# P_loha_E.net
KiCad netlist of a schematic drawn in EasyEDA Pro
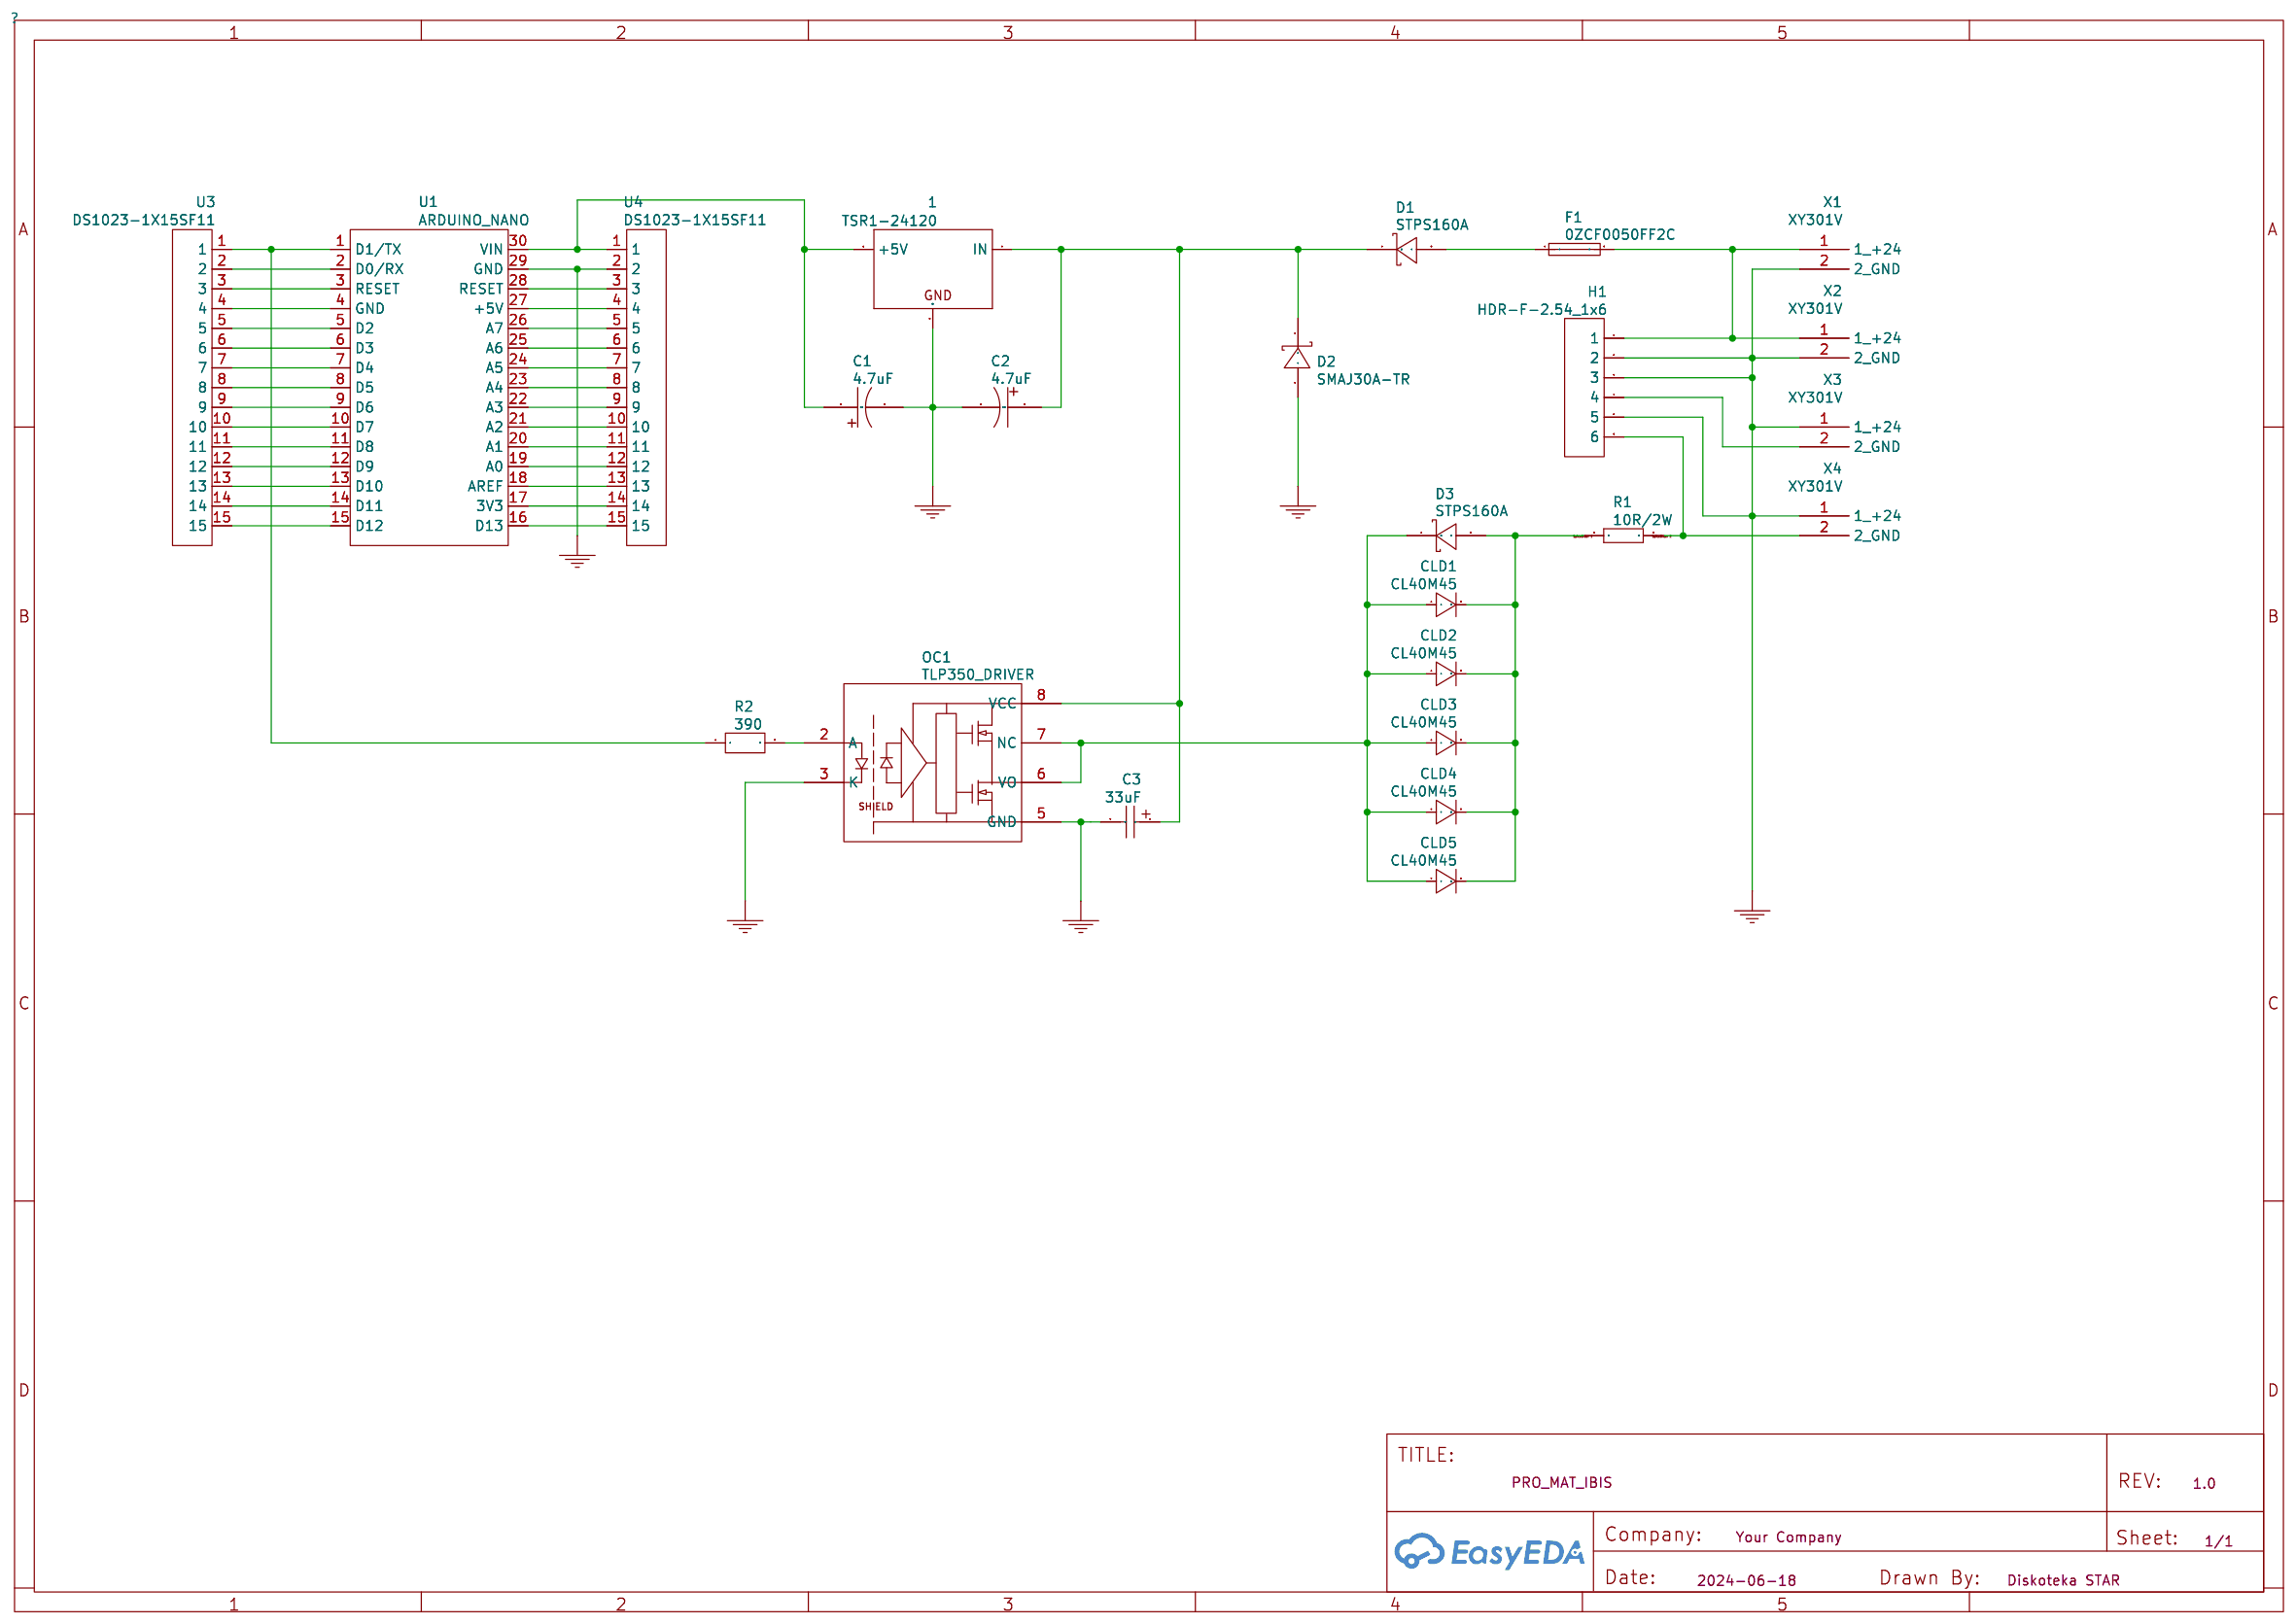
[diagram p0: schematic sheet]

(export (version "E")
  (design (tool "Eeschema 10.0.6"))
  (components
    (comp (ref "1") (value "TSR1-24120") (libsource (lib "easyedapro") (part "TSR1-24120")))
    (comp (ref "C1")
      (value "4.7uF")
      (fields
        (field (name "Manufacturer Part") "293D475X9035B2TE3")
        (field (name "Manufacturer") "VISHAY(威世)")
      )
      (libsource (lib "easyedapro") (part "4.7uF"))
    )
    (comp (ref "C2")
      (value "4.7uF")
      (fields
        (field (name "Manufacturer Part") "293D475X9035B2TE3")
        (field (name "Manufacturer") "VISHAY(威世)")
      )
      (libsource (lib "easyedapro") (part "4.7uF"))
    )
    (comp (ref "C3")
      (value "33uF")
      (fields
        (field (name "Manufacturer Part") "TPSD336K035R0300")
        (field (name "Manufacturer") "Kyocera AVX")
      )
      (libsource (lib "easyedapro") (part "33uF"))
    )
    (comp (ref "CLD1")
      (value "CL40M45")
      (fields (field (name "Manufacturer Part") "LL4148-GS08") (field (name "Manufacturer") "DIO"))
      (libsource (lib "easyedapro") (part "CL40M45"))
    )
    (comp (ref "CLD2")
      (value "CL40M45")
      (fields (field (name "Manufacturer Part") "LL4148-GS08") (field (name "Manufacturer") "DIO"))
      (libsource (lib "easyedapro") (part "CL40M45"))
    )
    (comp (ref "CLD3")
      (value "CL40M45")
      (fields (field (name "Manufacturer Part") "LL4148-GS08") (field (name "Manufacturer") "DIO"))
      (libsource (lib "easyedapro") (part "CL40M45"))
    )
    (comp (ref "CLD4")
      (value "CL40M45")
      (fields (field (name "Manufacturer Part") "LL4148-GS08") (field (name "Manufacturer") "DIO"))
      (libsource (lib "easyedapro") (part "CL40M45"))
    )
    (comp (ref "CLD5")
      (value "CL40M45")
      (fields (field (name "Manufacturer Part") "LL4148-GS08") (field (name "Manufacturer") "DIO"))
      (libsource (lib "easyedapro") (part "CL40M45"))
    )
    (comp (ref "D1")
      (value "STPS160A")
      (fields (field (name "Manufacturer") "ST(意法半导体)"))
      (libsource (lib "easyedapro") (part "STPS160A"))
    )
    (comp (ref "D2")
      (value "SMAJ30A-TR")
      (fields (field (name "Manufacturer") "ST(意法半导体)"))
      (libsource (lib "easyedapro") (part "SMAJ30A-TR"))
    )
    (comp (ref "D3")
      (value "STPS160A")
      (fields (field (name "Manufacturer") "ST(意法半导体)"))
      (libsource (lib "easyedapro") (part "STPS160A"))
    )
    (comp (ref "F1")
      (value "0ZCF0050FF2C")
      (fields (field (name "Manufacturer Part") "530-0ZCF0050FF2C") (field (name "Manufacturer") "Bel Fuse"))
      (libsource (lib "easyedapro") (part "0ZCF0050FF2C"))
    )
    (comp (ref "H1") (value "HDR-F-2.54_1x6") (libsource (lib "easyedapro") (part "HDR-F-2.54_1x6")))
    (comp (ref "OC1")
      (value "TLP350_DRIVER")
      (fields (field (name "Manufacturer Part") "TLP350(F)") (field (name "Manufacturer") "TOSHIBA(东芝)"))
      (libsource (lib "easyedapro") (part "TLP350_DRIVER"))
    )
    (comp (ref "R1") (value "10R/2W") (libsource (lib "easyedapro") (part "10R/2W")))
    (comp (ref "R2") (value "390") (libsource (lib "easyedapro") (part "390")))
    (comp (ref "U1") (value "ARDUINO_NANO") (libsource (lib "easyedapro") (part "ARDUINO_NANO")))
    (comp (ref "U3")
      (value "DS1023-1X15SF11")
      (fields (field (name "Manufacturer Part") "DS1023-1x15SF11") (field (name "Manufacturer") "CONNFLY"))
      (libsource (lib "easyedapro") (part "DS1023-1X15SF11"))
    )
    (comp (ref "U4")
      (value "DS1023-1X15SF11")
      (fields (field (name "Manufacturer Part") "DS1023-1x15SF11") (field (name "Manufacturer") "CONNFLY"))
      (libsource (lib "") (part "DS1023-1X15SF11_1"))
    )
    (comp (ref "X1")
      (value "XY301V")
      (fields
        (field (name "Manufacturer Part") "XY301V-A-5.0-2P")
        (field (name "Manufacturer") "XINLAIYA(新莱亚)")
      )
      (libsource (lib "easyedapro") (part "XY301V"))
    )
    (comp (ref "X2")
      (value "XY301V")
      (fields
        (field (name "Manufacturer Part") "XY301V-A-5.0-2P")
        (field (name "Manufacturer") "XINLAIYA(新莱亚)")
      )
      (libsource (lib "easyedapro") (part "XY301V"))
    )
    (comp (ref "X3")
      (value "XY301V")
      (fields
        (field (name "Manufacturer Part") "XY301V-A-5.0-2P")
        (field (name "Manufacturer") "XINLAIYA(新莱亚)")
      )
      (libsource (lib "easyedapro") (part "XY301V"))
    )
    (comp (ref "X4")
      (value "XY301V")
      (fields
        (field (name "Manufacturer Part") "XY301V-A-5.0-2P")
        (field (name "Manufacturer") "XINLAIYA(新莱亚)")
      )
      (libsource (lib "easyedapro") (part "XY301V"))
    )
  )
  (nets
    (net (code "1") (name "GND") (class "Default")
      (node (ref "1") (pin "2") (pinfunction "GND_2") (pintype "bidirectional"))
      (node (ref "C1") (pin "2") (pinfunction "2_2") (pintype "unspecified"))
      (node (ref "C2") (pin "2") (pinfunction "2_2") (pintype "unspecified"))
      (node (ref "C3") (pin "2") (pinfunction "2_2") (pintype "input"))
      (node (ref "D2") (pin "2") (pinfunction "A_2") (pintype "unspecified"))
      (node (ref "H1") (pin "2") (pinfunction "2_2") (pintype "input"))
      (node (ref "H1") (pin "3") (pinfunction "3_3") (pintype "input"))
      (node (ref "H1") (pin "5") (pinfunction "5_5") (pintype "input"))
      (node (ref "OC1") (pin "3") (pinfunction "K_3") (pintype "unspecified"))
      (node (ref "OC1") (pin "5") (pinfunction "GND_5") (pintype "unspecified"))
      (node (ref "U1") (pin "29") (pinfunction "GND_29") (pintype "unspecified"))
      (node (ref "U4") (pin "2") (pinfunction "2_2") (pintype "unspecified"))
      (node (ref "X1") (pin "2") (pinfunction "2_GND_2") (pintype "unspecified"))
      (node (ref "X2") (pin "2") (pinfunction "2_GND_2") (pintype "unspecified"))
      (node (ref "X3") (pin "1") (pinfunction "1_+24_1") (pintype "unspecified"))
      (node (ref "X4") (pin "1") (pinfunction "1_+24_1") (pintype "unspecified"))
    )
    (net (code "2") (name "Net-(1-+5V)") (class "Default")
      (node (ref "1") (pin "3") (pinfunction "+5V_3") (pintype "bidirectional"))
      (node (ref "C1") (pin "1") (pinfunction "1_1") (pintype "unspecified"))
      (node (ref "U1") (pin "30") (pinfunction "VIN_30") (pintype "unspecified"))
      (node (ref "U4") (pin "1") (pinfunction "1_1") (pintype "unspecified"))
    )
    (net (code "3") (name "Net-(1-IN)") (class "Default")
      (node (ref "1") (pin "1") (pinfunction "IN_1") (pintype "bidirectional"))
      (node (ref "C2") (pin "1") (pinfunction "1_1") (pintype "unspecified"))
      (node (ref "C3") (pin "1") (pinfunction "1_1") (pintype "input"))
      (node (ref "D1") (pin "1") (pinfunction "C_1") (pintype "unspecified"))
      (node (ref "D2") (pin "1") (pinfunction "K_1") (pintype "unspecified"))
      (node (ref "OC1") (pin "8") (pinfunction "VCC_8") (pintype "unspecified"))
    )
    (net (code "4") (name "Net-(CLD1-A)") (class "Default")
      (node (ref "CLD1") (pin "1") (pinfunction "A_1") (pintype "unspecified"))
      (node (ref "CLD2") (pin "1") (pinfunction "A_1") (pintype "unspecified"))
      (node (ref "CLD3") (pin "1") (pinfunction "A_1") (pintype "unspecified"))
      (node (ref "CLD4") (pin "1") (pinfunction "A_1") (pintype "unspecified"))
      (node (ref "CLD5") (pin "1") (pinfunction "A_1") (pintype "unspecified"))
      (node (ref "D3") (pin "1") (pinfunction "C_1") (pintype "unspecified"))
      (node (ref "OC1") (pin "6") (pinfunction "VO_6") (pintype "unspecified"))
      (node (ref "OC1") (pin "7") (pinfunction "NC_7") (pintype "unspecified"))
    )
    (net (code "5") (name "Net-(CLD1-C)") (class "Default")
      (node (ref "CLD1") (pin "2") (pinfunction "C_2") (pintype "unspecified"))
      (node (ref "CLD2") (pin "2") (pinfunction "C_2") (pintype "unspecified"))
      (node (ref "CLD3") (pin "2") (pinfunction "C_2") (pintype "unspecified"))
      (node (ref "CLD4") (pin "2") (pinfunction "C_2") (pintype "unspecified"))
      (node (ref "CLD5") (pin "2") (pinfunction "C_2") (pintype "unspecified"))
      (node (ref "D3") (pin "2") (pinfunction "A_2") (pintype "unspecified"))
      (node (ref "R1") (pin "1") (pinfunction "1_1") (pintype "bidirectional"))
    )
    (net (code "6") (name "Net-(D1-A)") (class "Default")
      (node (ref "D1") (pin "2") (pinfunction "A_2") (pintype "unspecified"))
      (node (ref "F1") (pin "1") (pinfunction "1_1") (pintype "unspecified"))
    )
    (net (code "7") (name "Net-(OC1-A)") (class "Default")
      (node (ref "OC1") (pin "2") (pinfunction "A_2") (pintype "unspecified"))
      (node (ref "R2") (pin "2") (pinfunction "2_2") (pintype "unspecified"))
    )
    (net (code "8") (name "Net-(U1-+5V)") (class "Default")
      (node (ref "U1") (pin "27") (pinfunction "+5V_27") (pintype "unspecified"))
      (node (ref "U4") (pin "4") (pinfunction "4_4") (pintype "unspecified"))
    )
    (net (code "9") (name "Net-(U1-3V3)") (class "Default")
      (node (ref "U1") (pin "17") (pinfunction "3V3_17") (pintype "unspecified"))
      (node (ref "U4") (pin "14") (pinfunction "14_14") (pintype "unspecified"))
    )
    (net (code "10") (name "Net-(U1-A0)") (class "Default")
      (node (ref "U1") (pin "19") (pinfunction "A0_19") (pintype "unspecified"))
      (node (ref "U4") (pin "12") (pinfunction "12_12") (pintype "unspecified"))
    )
    (net (code "11") (name "Net-(U1-A1)") (class "Default")
      (node (ref "U1") (pin "20") (pinfunction "A1_20") (pintype "unspecified"))
      (node (ref "U4") (pin "11") (pinfunction "11_11") (pintype "unspecified"))
    )
    (net (code "12") (name "Net-(U1-A2)") (class "Default")
      (node (ref "U1") (pin "21") (pinfunction "A2_21") (pintype "unspecified"))
      (node (ref "U4") (pin "10") (pinfunction "10_10") (pintype "unspecified"))
    )
    (net (code "13") (name "Net-(U1-A3)") (class "Default")
      (node (ref "U1") (pin "22") (pinfunction "A3_22") (pintype "unspecified"))
      (node (ref "U4") (pin "9") (pinfunction "9_9") (pintype "unspecified"))
    )
    (net (code "14") (name "Net-(U1-A4)") (class "Default")
      (node (ref "U1") (pin "23") (pinfunction "A4_23") (pintype "unspecified"))
      (node (ref "U4") (pin "8") (pinfunction "8_8") (pintype "unspecified"))
    )
    (net (code "15") (name "Net-(U1-A5)") (class "Default")
      (node (ref "U1") (pin "24") (pinfunction "A5_24") (pintype "unspecified"))
      (node (ref "U4") (pin "7") (pinfunction "7_7") (pintype "unspecified"))
    )
    (net (code "16") (name "Net-(U1-A6)") (class "Default")
      (node (ref "U1") (pin "25") (pinfunction "A6_25") (pintype "unspecified"))
      (node (ref "U4") (pin "6") (pinfunction "6_6") (pintype "unspecified"))
    )
    (net (code "17") (name "Net-(U1-A7)") (class "Default")
      (node (ref "U1") (pin "26") (pinfunction "A7_26") (pintype "unspecified"))
      (node (ref "U4") (pin "5") (pinfunction "5_5") (pintype "unspecified"))
    )
    (net (code "18") (name "Net-(U1-AREF)") (class "Default")
      (node (ref "U1") (pin "18") (pinfunction "AREF_18") (pintype "unspecified"))
      (node (ref "U4") (pin "13") (pinfunction "13_13") (pintype "unspecified"))
    )
    (net (code "19") (name "Net-(U1-D0{slash}RX)") (class "Default")
      (node (ref "U1") (pin "2") (pinfunction "D0/RX_2") (pintype "unspecified"))
      (node (ref "U3") (pin "2") (pinfunction "2_2") (pintype "unspecified"))
    )
    (net (code "20") (name "Net-(U1-D1{slash}TX)") (class "Default")
      (node (ref "R2") (pin "1") (pinfunction "1_1") (pintype "unspecified"))
      (node (ref "U1") (pin "1") (pinfunction "D1/TX_1") (pintype "unspecified"))
      (node (ref "U3") (pin "1") (pinfunction "1_1") (pintype "unspecified"))
    )
    (net (code "21") (name "Net-(U1-D2)") (class "Default")
      (node (ref "U1") (pin "5") (pinfunction "D2_5") (pintype "unspecified"))
      (node (ref "U3") (pin "5") (pinfunction "5_5") (pintype "unspecified"))
    )
    (net (code "22") (name "Net-(U1-D3)") (class "Default")
      (node (ref "U1") (pin "6") (pinfunction "D3_6") (pintype "unspecified"))
      (node (ref "U3") (pin "6") (pinfunction "6_6") (pintype "unspecified"))
    )
    (net (code "23") (name "Net-(U1-D4)") (class "Default")
      (node (ref "U1") (pin "7") (pinfunction "D4_7") (pintype "unspecified"))
      (node (ref "U3") (pin "7") (pinfunction "7_7") (pintype "unspecified"))
    )
    (net (code "24") (name "Net-(U1-D5)") (class "Default")
      (node (ref "U1") (pin "8") (pinfunction "D5_8") (pintype "unspecified"))
      (node (ref "U3") (pin "8") (pinfunction "8_8") (pintype "unspecified"))
    )
    (net (code "25") (name "Net-(U1-D6)") (class "Default")
      (node (ref "U1") (pin "9") (pinfunction "D6_9") (pintype "unspecified"))
      (node (ref "U3") (pin "9") (pinfunction "9_9") (pintype "unspecified"))
    )
    (net (code "26") (name "Net-(U1-D7)") (class "Default")
      (node (ref "U1") (pin "10") (pinfunction "D7_10") (pintype "unspecified"))
      (node (ref "U3") (pin "10") (pinfunction "10_10") (pintype "unspecified"))
    )
    (net (code "27") (name "Net-(U1-D8)") (class "Default")
      (node (ref "U1") (pin "11") (pinfunction "D8_11") (pintype "unspecified"))
      (node (ref "U3") (pin "11") (pinfunction "11_11") (pintype "unspecified"))
    )
    (net (code "28") (name "Net-(U1-D9)") (class "Default")
      (node (ref "U1") (pin "12") (pinfunction "D9_12") (pintype "unspecified"))
      (node (ref "U3") (pin "12") (pinfunction "12_12") (pintype "unspecified"))
    )
    (net (code "29") (name "Net-(U1-D10)") (class "Default")
      (node (ref "U1") (pin "13") (pinfunction "D10_13") (pintype "unspecified"))
      (node (ref "U3") (pin "13") (pinfunction "13_13") (pintype "unspecified"))
    )
    (net (code "30") (name "Net-(U1-D11)") (class "Default")
      (node (ref "U1") (pin "14") (pinfunction "D11_14") (pintype "unspecified"))
      (node (ref "U3") (pin "14") (pinfunction "14_14") (pintype "unspecified"))
    )
    (net (code "31") (name "Net-(U1-D12)") (class "Default")
      (node (ref "U1") (pin "15") (pinfunction "D12_15") (pintype "unspecified"))
      (node (ref "U3") (pin "15") (pinfunction "15_15") (pintype "unspecified"))
    )
    (net (code "32") (name "Net-(U1-D13)") (class "Default")
      (node (ref "U1") (pin "16") (pinfunction "D13_16") (pintype "unspecified"))
      (node (ref "U4") (pin "15") (pinfunction "15_15") (pintype "unspecified"))
    )
    (net (code "33") (name "Net-(U1-GND-Pad4)") (class "Default")
      (node (ref "U1") (pin "4") (pinfunction "GND_4") (pintype "unspecified"))
      (node (ref "U3") (pin "4") (pinfunction "4_4") (pintype "unspecified"))
    )
    (net (code "34") (name "Net-(U1-RESET-Pad3)") (class "Default")
      (node (ref "U1") (pin "3") (pinfunction "RESET_3") (pintype "unspecified"))
      (node (ref "U3") (pin "3") (pinfunction "3_3") (pintype "unspecified"))
    )
    (net (code "35") (name "Net-(U1-RESET-Pad28)") (class "Default")
      (node (ref "U1") (pin "28") (pinfunction "RESET_28") (pintype "unspecified"))
      (node (ref "U4") (pin "3") (pinfunction "3_3") (pintype "unspecified"))
    )
    (net (code "36") (name "Net-(X1-1_+24)") (class "Default")
      (node (ref "F1") (pin "2") (pinfunction "2_2") (pintype "unspecified"))
      (node (ref "H1") (pin "1") (pinfunction "1_1") (pintype "input"))
      (node (ref "X1") (pin "1") (pinfunction "1_+24_1") (pintype "unspecified"))
      (node (ref "X2") (pin "1") (pinfunction "1_+24_1") (pintype "unspecified"))
    )
    (net (code "37") (name "Net-(X3-2_GND)") (class "Default")
      (node (ref "H1") (pin "4") (pinfunction "4_4") (pintype "input"))
      (node (ref "X3") (pin "2") (pinfunction "2_GND_2") (pintype "unspecified"))
    )
    (net (code "38") (name "Net-(X4-2_GND)") (class "Default")
      (node (ref "H1") (pin "6") (pinfunction "6_6") (pintype "input"))
      (node (ref "R1") (pin "2") (pinfunction "2_2") (pintype "bidirectional"))
      (node (ref "X4") (pin "2") (pinfunction "2_GND_2") (pintype "unspecified"))
    )
  )
)
